# v1.net
KiCad netlist of a schematic drawn in EAGLE
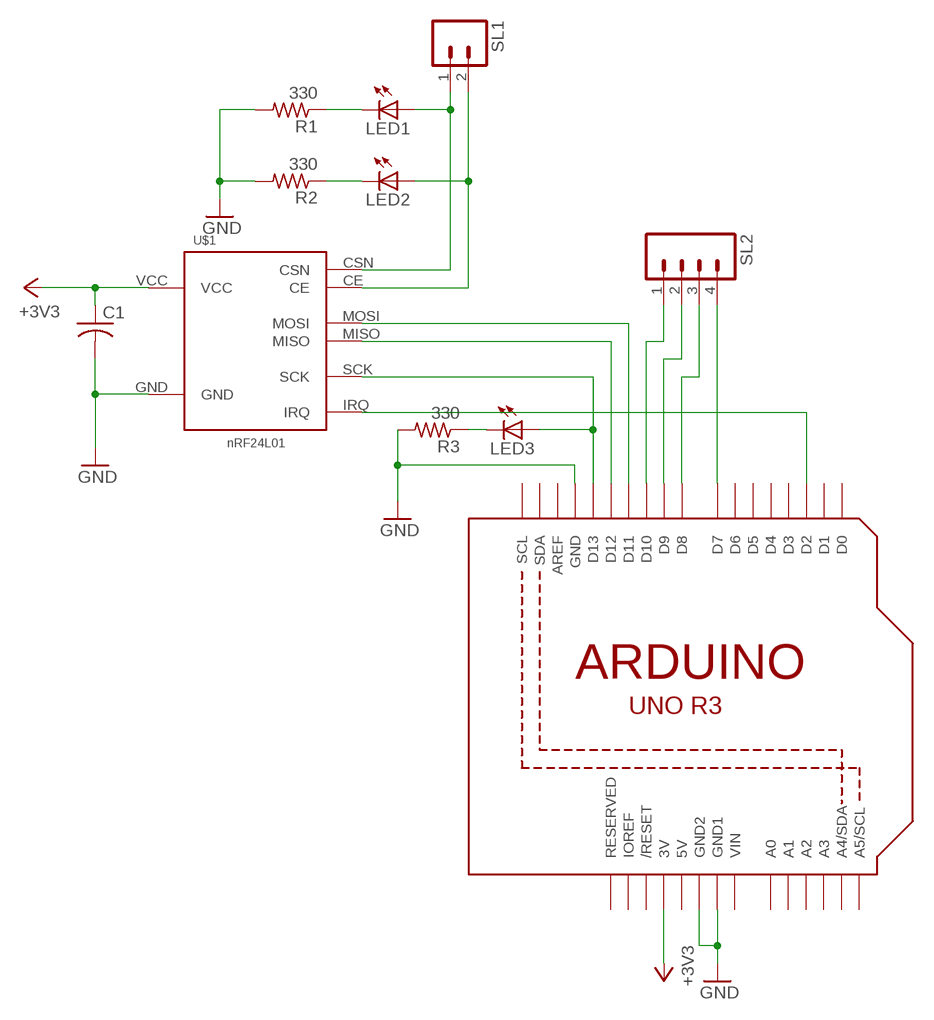
[diagram p0: schematic, sheet 1]

(export (version "E")
  (design (tool "Eeschema 10.0.6"))
  (components
    (comp (ref "C1")
      (value "C-USC0603")
      (footprint "eagle-import:C0603")
      (libsource (lib "eagle-import") (part "C-USC0603"))
    )
    (comp (ref "LED1")
      (value "LED5MM")
      (footprint "eagle-import:LED5MM")
      (libsource (lib "eagle-import") (part "LED5MM"))
    )
    (comp (ref "LED2")
      (value "LED5MM")
      (footprint "eagle-import:LED5MM")
      (libsource (lib "eagle-import") (part "LED5MM"))
    )
    (comp (ref "LED3")
      (value "LED5MM")
      (footprint "eagle-import:LED5MM")
      (libsource (lib "eagle-import") (part "LED5MM"))
    )
    (comp (ref "R1")
      (value "330")
      (footprint "eagle-import:R0603")
      (libsource (lib "eagle-import") (part "R-US_R0603"))
    )
    (comp (ref "R2")
      (value "330")
      (footprint "eagle-import:R0603")
      (libsource (lib "eagle-import") (part "R-US_R0603"))
    )
    (comp (ref "R3")
      (value "330")
      (footprint "eagle-import:R0603")
      (libsource (lib "eagle-import") (part "R-US_R0603"))
    )
    (comp (ref "SL1")
      (value "M02")
      (footprint "eagle-import:02P")
      (libsource (lib "eagle-import") (part "M02"))
    )
    (comp (ref "SL2")
      (value "M04")
      (footprint "eagle-import:04P")
      (libsource (lib "eagle-import") (part "M04"))
    )
    (comp (ref "U$1")
      (value "NRF24L01MODULE")
      (footprint "eagle-import:NRF24L01-MODULE")
      (libsource (lib "eagle-import") (part "NRF24L01MODULE"))
    )
    (comp (ref "U1")
      (value "ARDUINOR3-DIMENSION")
      (footprint "eagle-import:ARDUINOR3")
      (libsource (lib "eagle-import") (part "ARDUINOR3-DIMENSION"))
    )
  )
  (nets
    (net (code "1") (name "+3V3") (class "Default")
      (node (ref "C1") (pin "1") (pinfunction "1_1") (pintype "passive"))
      (node (ref "U$1") (pin "VCC") (pinfunction "VCC_VCC") (pintype "power_in"))
      (node (ref "U1") (pin "3V") (pinfunction "3V_3V") (pintype "power_in"))
    )
    (net (code "2") (name "/5V") (class "Default")
      (node (ref "U1") (pin "5V") (pinfunction "5V_5V") (pintype "power_in"))
    )
    (net (code "3") (name "/VIN") (class "Default")
      (node (ref "U1") (pin "VIN") (pinfunction "VIN_VIN") (pintype "power_in"))
    )
    (net (code "4") (name "GND") (class "Default")
      (node (ref "C1") (pin "2") (pinfunction "2_2") (pintype "passive"))
      (node (ref "R1") (pin "2") (pinfunction "2_2") (pintype "passive"))
      (node (ref "R2") (pin "2") (pinfunction "2_2") (pintype "passive"))
      (node (ref "R3") (pin "2") (pinfunction "2_2") (pintype "passive"))
      (node (ref "U$1") (pin "GND") (pinfunction "GND_GND") (pintype "power_in"))
      (node (ref "U1") (pin "GND") (pinfunction "GND_GND") (pintype "power_in"))
      (node (ref "U1") (pin "GND1") (pinfunction "GND1_GND1") (pintype "power_in"))
      (node (ref "U1") (pin "GND2") (pinfunction "GND2_GND2") (pintype "power_in"))
    )
    (net (code "5") (name "Net-(LED1-C)") (class "Default")
      (node (ref "LED1") (pin "K") (pinfunction "C_K") (pintype "passive"))
      (node (ref "R1") (pin "1") (pinfunction "1_1") (pintype "passive"))
    )
    (net (code "6") (name "Net-(LED1-PadA)") (class "Default")
      (node (ref "LED1") (pin "A") (pinfunction "A_A") (pintype "passive"))
      (node (ref "SL1") (pin "1") (pinfunction "1_1") (pintype "passive"))
      (node (ref "U$1") (pin "CSN") (pinfunction "CSN_CSN") (pintype "bidirectional"))
    )
    (net (code "7") (name "Net-(LED2-C)") (class "Default")
      (node (ref "LED2") (pin "K") (pinfunction "C_K") (pintype "passive"))
      (node (ref "R2") (pin "1") (pinfunction "1_1") (pintype "passive"))
    )
    (net (code "8") (name "Net-(LED2-PadA)") (class "Default")
      (node (ref "LED2") (pin "A") (pinfunction "A_A") (pintype "passive"))
      (node (ref "SL1") (pin "2") (pinfunction "2_2") (pintype "passive"))
      (node (ref "U$1") (pin "CE") (pinfunction "CE_CE") (pintype "bidirectional"))
    )
    (net (code "9") (name "Net-(LED3-C)") (class "Default")
      (node (ref "LED3") (pin "K") (pinfunction "C_K") (pintype "passive"))
      (node (ref "R3") (pin "1") (pinfunction "1_1") (pintype "passive"))
    )
    (net (code "10") (name "Net-(LED3-PadA)") (class "Default")
      (node (ref "LED3") (pin "A") (pinfunction "A_A") (pintype "passive"))
      (node (ref "U$1") (pin "SCK") (pinfunction "SCK_SCK") (pintype "bidirectional"))
      (node (ref "U1") (pin "D13") (pinfunction "D13_D13") (pintype "bidirectional"))
    )
    (net (code "11") (name "Net-(SL2-Pad1)") (class "Default")
      (node (ref "SL2") (pin "1") (pinfunction "1_1") (pintype "passive"))
      (node (ref "U1") (pin "D10") (pinfunction "D10_D10") (pintype "bidirectional"))
    )
    (net (code "12") (name "Net-(SL2-Pad2)") (class "Default")
      (node (ref "SL2") (pin "2") (pinfunction "2_2") (pintype "passive"))
      (node (ref "U1") (pin "D9") (pinfunction "D9_D9") (pintype "bidirectional"))
    )
    (net (code "13") (name "Net-(SL2-Pad3)") (class "Default")
      (node (ref "SL2") (pin "3") (pinfunction "3_3") (pintype "passive"))
      (node (ref "U1") (pin "D8") (pinfunction "D8_D8") (pintype "bidirectional"))
    )
    (net (code "14") (name "Net-(SL2-Pad4)") (class "Default")
      (node (ref "SL2") (pin "4") (pinfunction "4_4") (pintype "passive"))
      (node (ref "U1") (pin "D7") (pinfunction "D7_D7") (pintype "bidirectional"))
    )
    (net (code "15") (name "Net-(U$1-PadIRQ)") (class "Default")
      (node (ref "U$1") (pin "IRQ") (pinfunction "IRQ_IRQ") (pintype "bidirectional"))
      (node (ref "U1") (pin "D2") (pinfunction "D2_D2") (pintype "bidirectional"))
    )
    (net (code "16") (name "Net-(U$1-PadMISO)") (class "Default")
      (node (ref "U$1") (pin "MISO") (pinfunction "MISO_MISO") (pintype "bidirectional"))
      (node (ref "U1") (pin "D12") (pinfunction "D12_D12") (pintype "bidirectional"))
    )
    (net (code "17") (name "Net-(U$1-PadMOSI)") (class "Default")
      (node (ref "U$1") (pin "MOSI") (pinfunction "MOSI_MOSI") (pintype "bidirectional"))
      (node (ref "U1") (pin "D11") (pinfunction "D11_D11") (pintype "bidirectional"))
    )
    (net (code "18") (name "unconnected-(U1-A4{slash}SDA-PadA4)") (class "Default")
      (node (ref "U1") (pin "A4") (pinfunction "A4/SDA_A4") (pintype "bidirectional"))
    )
    (net (code "19") (name "unconnected-(U1-A5{slash}SCL-PadA5)") (class "Default")
      (node (ref "U1") (pin "A5") (pinfunction "A5/SCL_A5") (pintype "bidirectional"))
    )
    (net (code "20") (name "unconnected-(U1-PadA0)") (class "Default")
      (node (ref "U1") (pin "A0") (pinfunction "A0_A0") (pintype "bidirectional"))
    )
    (net (code "21") (name "unconnected-(U1-PadA1)") (class "Default")
      (node (ref "U1") (pin "A1") (pinfunction "A1_A1") (pintype "bidirectional"))
    )
    (net (code "22") (name "unconnected-(U1-PadA2)") (class "Default")
      (node (ref "U1") (pin "A2") (pinfunction "A2_A2") (pintype "bidirectional"))
    )
    (net (code "23") (name "unconnected-(U1-PadA3)") (class "Default")
      (node (ref "U1") (pin "A3") (pinfunction "A3_A3") (pintype "bidirectional"))
    )
    (net (code "24") (name "unconnected-(U1-PadAREF)") (class "Default")
      (node (ref "U1") (pin "AREF") (pinfunction "AREF_AREF") (pintype "bidirectional"))
    )
    (net (code "25") (name "unconnected-(U1-PadD0)") (class "Default")
      (node (ref "U1") (pin "D0") (pinfunction "D0_D0") (pintype "bidirectional"))
    )
    (net (code "26") (name "unconnected-(U1-PadD1)") (class "Default")
      (node (ref "U1") (pin "D1") (pinfunction "D1_D1") (pintype "bidirectional"))
    )
    (net (code "27") (name "unconnected-(U1-PadD3)") (class "Default")
      (node (ref "U1") (pin "D3") (pinfunction "D3_D3") (pintype "bidirectional"))
    )
    (net (code "28") (name "unconnected-(U1-PadD4)") (class "Default")
      (node (ref "U1") (pin "D4") (pinfunction "D4_D4") (pintype "bidirectional"))
    )
    (net (code "29") (name "unconnected-(U1-PadD5)") (class "Default")
      (node (ref "U1") (pin "D5") (pinfunction "D5_D5") (pintype "bidirectional"))
    )
    (net (code "30") (name "unconnected-(U1-PadD6)") (class "Default")
      (node (ref "U1") (pin "D6") (pinfunction "D6_D6") (pintype "bidirectional"))
    )
    (net (code "31") (name "unconnected-(U1-PadIOREF)") (class "Default")
      (node (ref "U1") (pin "IOREF") (pinfunction "IOREF_IOREF") (pintype "output"))
    )
    (net (code "32") (name "unconnected-(U1-PadRESERVED)") (class "Default")
      (node (ref "U1") (pin "RESERVED") (pinfunction "RESERVED_RESERVED") (pintype "no_connect"))
    )
    (net (code "33") (name "unconnected-(U1-PadSCL)") (class "Default")
      (node (ref "U1") (pin "SCL") (pinfunction "SCL_SCL") (pintype "bidirectional"))
    )
    (net (code "34") (name "unconnected-(U1-PadSDA)") (class "Default")
      (node (ref "U1") (pin "SDA") (pinfunction "SDA_SDA") (pintype "bidirectional"))
    )
    (net (code "35") (name "unconnected-(U1-{slash}RESET-PadRESET)") (class "Default")
      (node (ref "U1") (pin "RESET") (pinfunction "/RESET_RESET") (pintype "bidirectional"))
    )
  )
)
